# BMS_ERROR_Detection.net
KiCad netlist of a schematic drawn in EAGLE
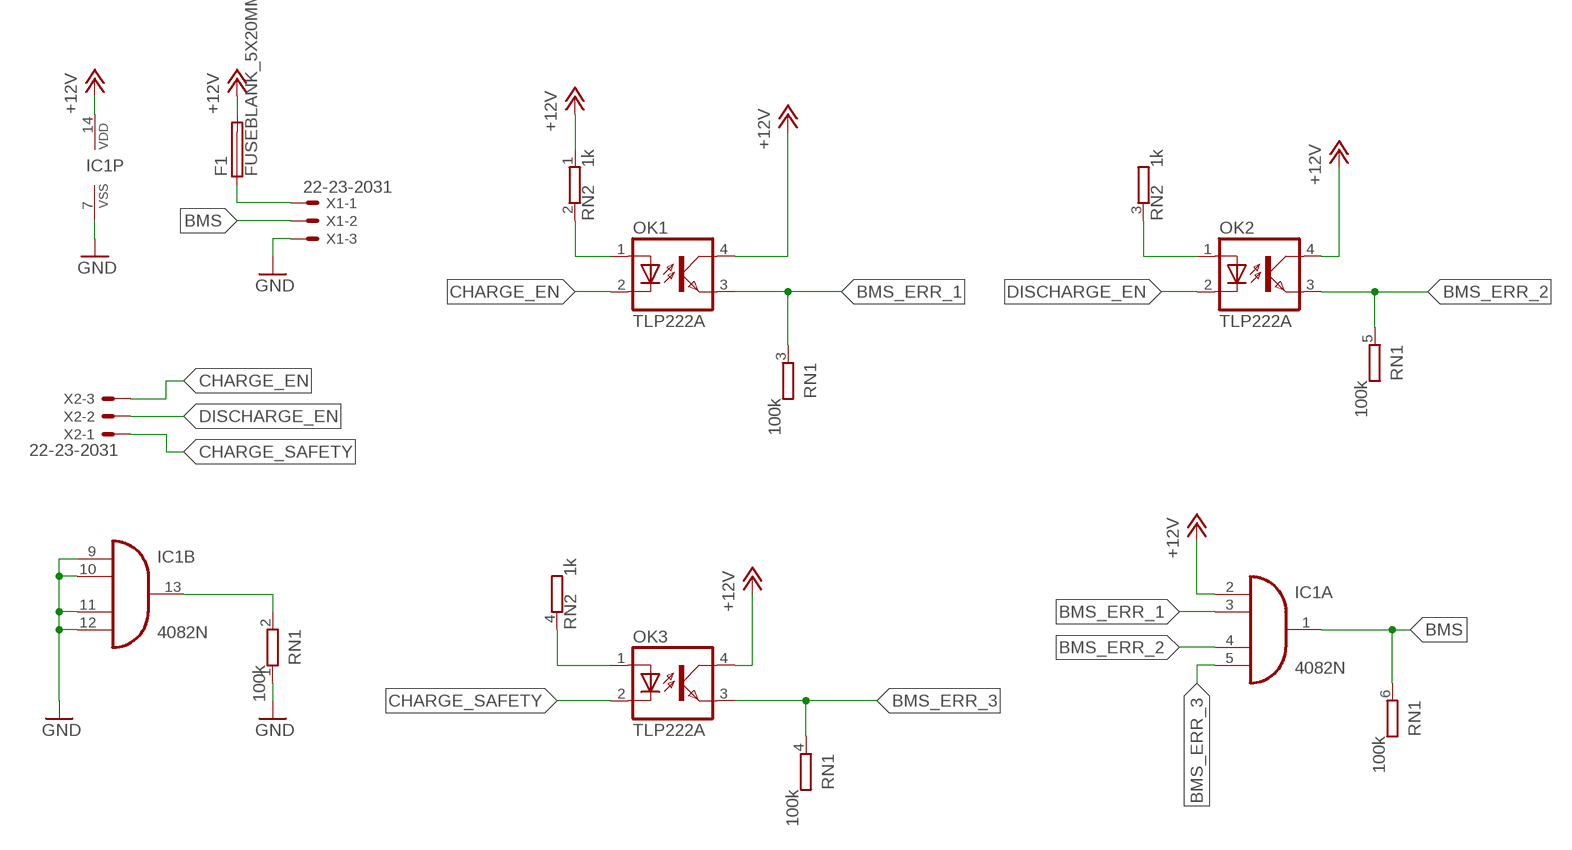
[diagram p0: schematic, sheet 1]

(export (version "E")
  (design (tool "Eeschema 10.0.6"))
  (components
    (comp (ref "F1")
      (value "FUSEBLANK_5X20MM")
      (footprint "eagle-import:FUSE_HOLDER_5X20MM")
      (libsource (lib "eagle-import") (part "FUSEBLANK_5X20MM"))
    )
    (comp (ref "IC1")
      (value "4082N")
      (footprint "eagle-import:DIL14")
      (libsource (lib "eagle-import") (part "4082N"))
    )
    (comp (ref "OK1")
      (value "TLP222A")
      (footprint "eagle-import:DIL04")
      (libsource (lib "eagle-import") (part "LTV816"))
    )
    (comp (ref "OK2")
      (value "TLP222A")
      (footprint "eagle-import:DIL04")
      (libsource (lib "eagle-import") (part "LTV816"))
    )
    (comp (ref "OK3")
      (value "TLP222A")
      (footprint "eagle-import:DIL04")
      (libsource (lib "eagle-import") (part "LTV816"))
    )
    (comp (ref "RN1")
      (value "100k")
      (footprint "eagle-import:SIL6")
      (libsource (lib "eagle-import") (part "GE05RP"))
    )
    (comp (ref "RN2")
      (value "1k")
      (footprint "eagle-import:SIL4")
      (libsource (lib "eagle-import") (part "GE03RP"))
    )
    (comp (ref "X1")
      (value "22-23-2031")
      (footprint "eagle-import:22-23-2031")
      (fields (field (name "MF") "MOLEX"))
      (libsource (lib "eagle-import") (part "22-23-2031"))
    )
    (comp (ref "X2")
      (value "22-23-2031")
      (footprint "eagle-import:22-23-2031")
      (fields (field (name "MF") "MOLEX"))
      (libsource (lib "eagle-import") (part "22-23-2031"))
    )
  )
  (nets
    (net (code "1") (name "+12V") (class "Default")
      (node (ref "F1") (pin "2") (pinfunction "2_2") (pintype "passive"))
      (node (ref "IC1") (pin "14") (pinfunction "VDD_14") (pintype "power_in"))
      (node (ref "IC1") (pin "2") (pinfunction "I0_2") (pintype "input"))
      (node (ref "OK1") (pin "4") (pinfunction "COL_4") (pintype "passive"))
      (node (ref "OK2") (pin "4") (pinfunction "COL_4") (pintype "passive"))
      (node (ref "OK3") (pin "4") (pinfunction "COL_4") (pintype "passive"))
      (node (ref "RN2") (pin "1") (pinfunction "1_1") (pintype "passive"))
    )
    (net (code "2") (name "BMS") (class "Default")
      (node (ref "IC1") (pin "1") (pinfunction "O_1") (pintype "output"))
      (node (ref "RN1") (pin "6") (pinfunction "2_6") (pintype "passive"))
      (node (ref "X1") (pin "2") (pinfunction "S_2") (pintype "passive"))
    )
    (net (code "3") (name "BMS_ERR_1") (class "Default")
      (node (ref "IC1") (pin "3") (pinfunction "I1_3") (pintype "input"))
      (node (ref "OK1") (pin "3") (pinfunction "EMIT_3") (pintype "passive"))
      (node (ref "RN1") (pin "3") (pinfunction "2_3") (pintype "passive"))
    )
    (net (code "4") (name "BMS_ERR_2") (class "Default")
      (node (ref "IC1") (pin "4") (pinfunction "I2_4") (pintype "input"))
      (node (ref "OK2") (pin "3") (pinfunction "EMIT_3") (pintype "passive"))
      (node (ref "RN1") (pin "5") (pinfunction "2_5") (pintype "passive"))
    )
    (net (code "5") (name "BMS_ERR_3") (class "Default")
      (node (ref "IC1") (pin "5") (pinfunction "I3_5") (pintype "input"))
      (node (ref "OK3") (pin "3") (pinfunction "EMIT_3") (pintype "passive"))
      (node (ref "RN1") (pin "4") (pinfunction "2_4") (pintype "passive"))
    )
    (net (code "6") (name "CHARGE_EN") (class "Default")
      (node (ref "OK1") (pin "2") (pinfunction "C_2") (pintype "passive"))
      (node (ref "X2") (pin "3") (pinfunction "S_3") (pintype "passive"))
    )
    (net (code "7") (name "CHARGE_SAFETY") (class "Default")
      (node (ref "OK3") (pin "2") (pinfunction "C_2") (pintype "passive"))
      (node (ref "X2") (pin "1") (pinfunction "S_1") (pintype "passive"))
    )
    (net (code "8") (name "DISCHARGE_EN") (class "Default")
      (node (ref "OK2") (pin "2") (pinfunction "C_2") (pintype "passive"))
      (node (ref "X2") (pin "2") (pinfunction "S_2") (pintype "passive"))
    )
    (net (code "9") (name "GND") (class "Default")
      (node (ref "IC1") (pin "10") (pinfunction "I1_10") (pintype "input"))
      (node (ref "IC1") (pin "11") (pinfunction "I2_11") (pintype "input"))
      (node (ref "IC1") (pin "12") (pinfunction "I3_12") (pintype "input"))
      (node (ref "IC1") (pin "7") (pinfunction "VSS_7") (pintype "power_in"))
      (node (ref "IC1") (pin "9") (pinfunction "I0_9") (pintype "input"))
      (node (ref "RN1") (pin "1") (pinfunction "1_1") (pintype "passive"))
      (node (ref "X1") (pin "3") (pinfunction "S_3") (pintype "passive"))
    )
    (net (code "10") (name "Net-(IC1B-O)") (class "Default")
      (node (ref "IC1") (pin "13") (pinfunction "O_13") (pintype "output"))
      (node (ref "RN1") (pin "2") (pinfunction "2_2") (pintype "passive"))
    )
    (net (code "11") (name "Net-(OK1-A)") (class "Default")
      (node (ref "OK1") (pin "1") (pinfunction "A_1") (pintype "passive"))
      (node (ref "RN2") (pin "2") (pinfunction "2_2") (pintype "passive"))
    )
    (net (code "12") (name "Net-(OK2-A)") (class "Default")
      (node (ref "OK2") (pin "1") (pinfunction "A_1") (pintype "passive"))
      (node (ref "RN2") (pin "3") (pinfunction "2_3") (pintype "passive"))
    )
    (net (code "13") (name "Net-(OK3-A)") (class "Default")
      (node (ref "OK3") (pin "1") (pinfunction "A_1") (pintype "passive"))
      (node (ref "RN2") (pin "4") (pinfunction "2_4") (pintype "passive"))
    )
    (net (code "14") (name "Net-(X1A-S)") (class "Default")
      (node (ref "F1") (pin "1") (pinfunction "1_1") (pintype "passive"))
      (node (ref "X1") (pin "1") (pinfunction "S_1") (pintype "passive"))
    )
  )
)
